# M623.net
KiCad netlist of a schematic drawn in EAGLE
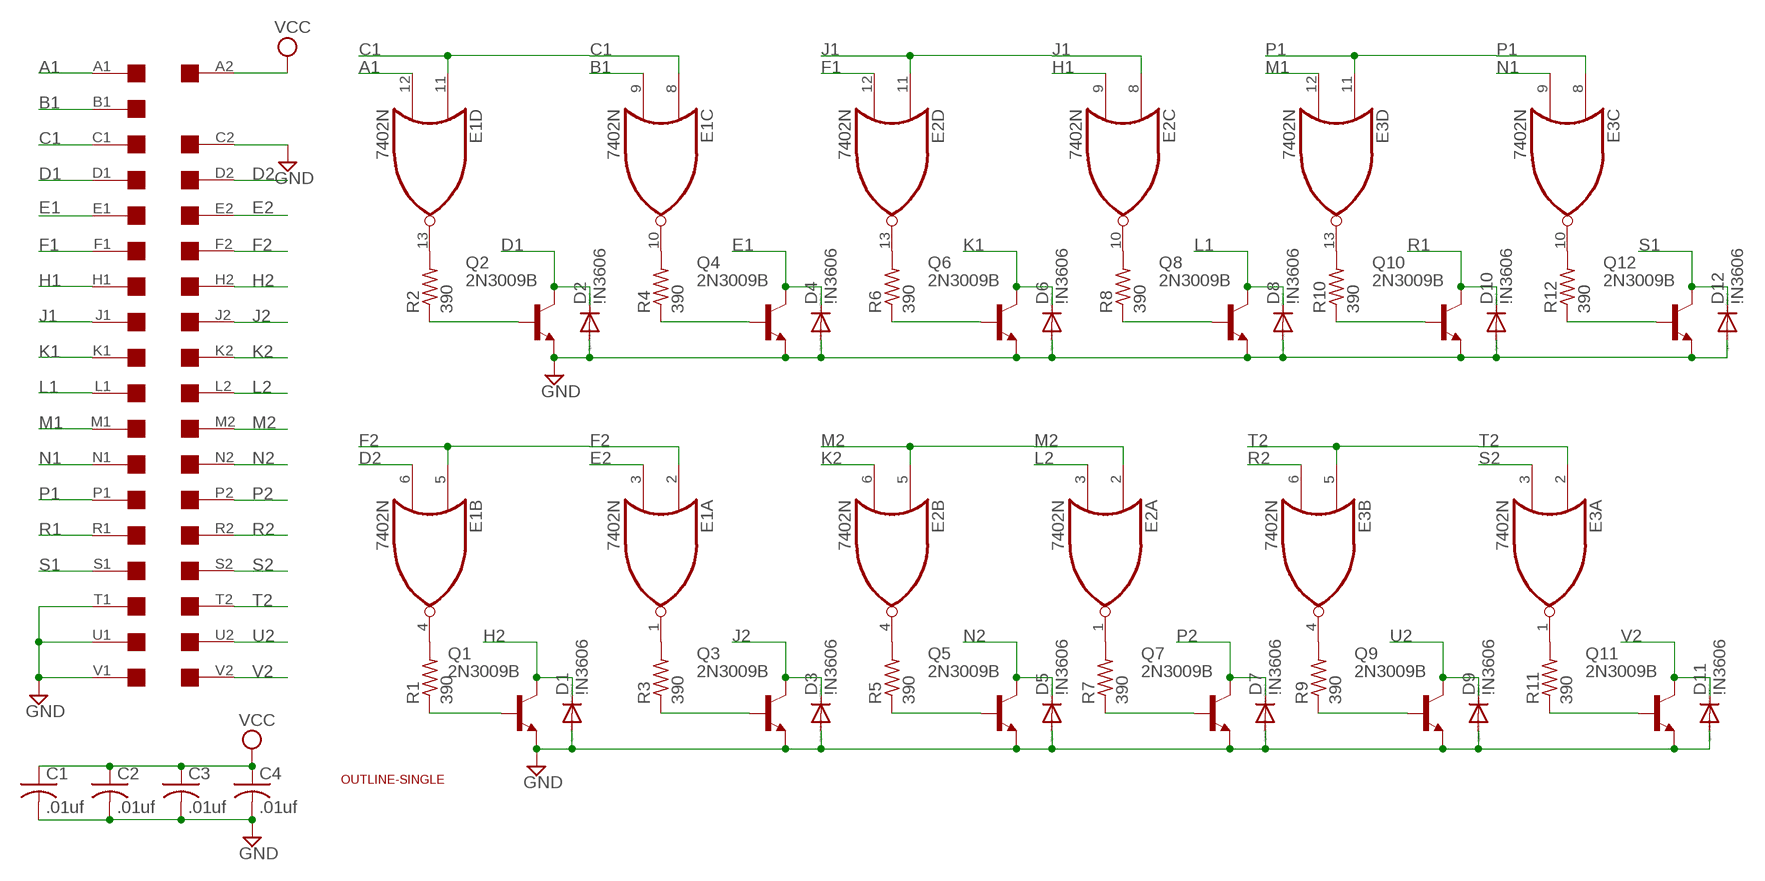
[diagram p0: schematic, sheet 1]

(export (version "E")
  (design (tool "Eeschema 10.0.6"))
  (components
    (comp (ref "C1")
      (value ".01uf")
      (footprint "eagle-import:C050-025X075")
      (libsource (lib "eagle-import") (part "C-US050-025X075"))
    )
    (comp (ref "C2")
      (value ".01uf")
      (footprint "eagle-import:C050-025X075")
      (libsource (lib "eagle-import") (part "C-US050-025X075"))
    )
    (comp (ref "C3")
      (value ".01uf")
      (footprint "eagle-import:C050-025X075")
      (libsource (lib "eagle-import") (part "C-US050-025X075"))
    )
    (comp (ref "C4")
      (value ".01uf")
      (footprint "eagle-import:C050-025X075")
      (libsource (lib "eagle-import") (part "C-US050-025X075"))
    )
    (comp (ref "D1")
      (value "\\!N3606")
      (footprint "eagle-import:DO35-10")
      (libsource (lib "eagle-import") (part "1N4148DO35-10"))
    )
    (comp (ref "D2")
      (value "\\!N3606")
      (footprint "eagle-import:DO35-10")
      (libsource (lib "eagle-import") (part "1N4148DO35-10"))
    )
    (comp (ref "D3")
      (value "\\!N3606")
      (footprint "eagle-import:DO35-10")
      (libsource (lib "eagle-import") (part "1N4148DO35-10"))
    )
    (comp (ref "D4")
      (value "\\!N3606")
      (footprint "eagle-import:DO35-10")
      (libsource (lib "eagle-import") (part "1N4148DO35-10"))
    )
    (comp (ref "D5")
      (value "\\!N3606")
      (footprint "eagle-import:DO35-10")
      (libsource (lib "eagle-import") (part "1N4148DO35-10"))
    )
    (comp (ref "D6")
      (value "\\!N3606")
      (footprint "eagle-import:DO35-10")
      (libsource (lib "eagle-import") (part "1N4148DO35-10"))
    )
    (comp (ref "D7")
      (value "\\!N3606")
      (footprint "eagle-import:DO35-10")
      (libsource (lib "eagle-import") (part "1N4148DO35-10"))
    )
    (comp (ref "D8")
      (value "\\!N3606")
      (footprint "eagle-import:DO35-10")
      (libsource (lib "eagle-import") (part "1N4148DO35-10"))
    )
    (comp (ref "D9")
      (value "\\!N3606")
      (footprint "eagle-import:DO35-10")
      (libsource (lib "eagle-import") (part "1N4148DO35-10"))
    )
    (comp (ref "D10")
      (value "\\!N3606")
      (footprint "eagle-import:DO35-10")
      (libsource (lib "eagle-import") (part "1N4148DO35-10"))
    )
    (comp (ref "D11")
      (value "\\!N3606")
      (footprint "eagle-import:DO35-10")
      (libsource (lib "eagle-import") (part "1N4148DO35-10"))
    )
    (comp (ref "D12")
      (value "\\!N3606")
      (footprint "eagle-import:DO35-10")
      (libsource (lib "eagle-import") (part "1N4148DO35-10"))
    )
    (comp (ref "E1")
      (value "7402N")
      (footprint "eagle-import:DIL14")
      (libsource (lib "eagle-import") (part "7402N"))
    )
    (comp (ref "E2")
      (value "7402N")
      (footprint "eagle-import:DIL14")
      (libsource (lib "eagle-import") (part "7402N"))
    )
    (comp (ref "E3")
      (value "7402N")
      (footprint "eagle-import:DIL14")
      (libsource (lib "eagle-import") (part "7402N"))
    )
    (comp (ref "Q1")
      (value "2N3009B")
      (footprint "eagle-import:TO39")
      (libsource (lib "eagle-import") (part "-NPN-TO39-EBC2N1613"))
    )
    (comp (ref "Q2")
      (value "2N3009B")
      (footprint "eagle-import:TO39")
      (libsource (lib "eagle-import") (part "-NPN-TO39-EBC2N1613"))
    )
    (comp (ref "Q3")
      (value "2N3009B")
      (footprint "eagle-import:TO39")
      (libsource (lib "eagle-import") (part "-NPN-TO39-EBC2N1613"))
    )
    (comp (ref "Q4")
      (value "2N3009B")
      (footprint "eagle-import:TO39")
      (libsource (lib "eagle-import") (part "-NPN-TO39-EBC2N1613"))
    )
    (comp (ref "Q5")
      (value "2N3009B")
      (footprint "eagle-import:TO39")
      (libsource (lib "eagle-import") (part "-NPN-TO39-EBC2N1613"))
    )
    (comp (ref "Q6")
      (value "2N3009B")
      (footprint "eagle-import:TO39")
      (libsource (lib "eagle-import") (part "-NPN-TO39-EBC2N1613"))
    )
    (comp (ref "Q7")
      (value "2N3009B")
      (footprint "eagle-import:TO39")
      (libsource (lib "eagle-import") (part "-NPN-TO39-EBC2N1613"))
    )
    (comp (ref "Q8")
      (value "2N3009B")
      (footprint "eagle-import:TO39")
      (libsource (lib "eagle-import") (part "-NPN-TO39-EBC2N1613"))
    )
    (comp (ref "Q9")
      (value "2N3009B")
      (footprint "eagle-import:TO39")
      (libsource (lib "eagle-import") (part "-NPN-TO39-EBC2N1613"))
    )
    (comp (ref "Q10")
      (value "2N3009B")
      (footprint "eagle-import:TO39")
      (libsource (lib "eagle-import") (part "-NPN-TO39-EBC2N1613"))
    )
    (comp (ref "Q11")
      (value "2N3009B")
      (footprint "eagle-import:TO39")
      (libsource (lib "eagle-import") (part "-NPN-TO39-EBC2N1613"))
    )
    (comp (ref "Q12")
      (value "2N3009B")
      (footprint "eagle-import:TO39")
      (libsource (lib "eagle-import") (part "-NPN-TO39-EBC2N1613"))
    )
    (comp (ref "R1")
      (value "390")
      (footprint "eagle-import:0207_10")
      (libsource (lib "eagle-import") (part "R-US_0207/10"))
    )
    (comp (ref "R2")
      (value "390")
      (footprint "eagle-import:0207_10")
      (libsource (lib "eagle-import") (part "R-US_0207/10"))
    )
    (comp (ref "R3")
      (value "390")
      (footprint "eagle-import:0207_10")
      (libsource (lib "eagle-import") (part "R-US_0207/10"))
    )
    (comp (ref "R4")
      (value "390")
      (footprint "eagle-import:0207_10")
      (libsource (lib "eagle-import") (part "R-US_0207/10"))
    )
    (comp (ref "R5")
      (value "390")
      (footprint "eagle-import:0207_10")
      (libsource (lib "eagle-import") (part "R-US_0207/10"))
    )
    (comp (ref "R6")
      (value "390")
      (footprint "eagle-import:0207_10")
      (libsource (lib "eagle-import") (part "R-US_0207/10"))
    )
    (comp (ref "R7")
      (value "390")
      (footprint "eagle-import:0207_10")
      (libsource (lib "eagle-import") (part "R-US_0207/10"))
    )
    (comp (ref "R8")
      (value "390")
      (footprint "eagle-import:0207_10")
      (libsource (lib "eagle-import") (part "R-US_0207/10"))
    )
    (comp (ref "R9")
      (value "390")
      (footprint "eagle-import:0207_10")
      (libsource (lib "eagle-import") (part "R-US_0207/10"))
    )
    (comp (ref "R10")
      (value "390")
      (footprint "eagle-import:0207_10")
      (libsource (lib "eagle-import") (part "R-US_0207/10"))
    )
    (comp (ref "R11")
      (value "390")
      (footprint "eagle-import:0207_10")
      (libsource (lib "eagle-import") (part "R-US_0207/10"))
    )
    (comp (ref "R12")
      (value "390")
      (footprint "eagle-import:0207_10")
      (libsource (lib "eagle-import") (part "R-US_0207/10"))
    )
    (comp (ref "U$1")
      (value "OUTLINE-SINGLE")
      (footprint "eagle-import:SINGLE")
      (libsource (lib "eagle-import") (part "OUTLINE-SINGLE"))
    )
    (comp (ref "U$4")
      (value "SINGLE")
      (footprint "eagle-import:EDGE-CON2")
      (libsource (lib "eagle-import") (part "SINGLE"))
    )
  )
  (nets
    (net (code "1") (name "/A1") (class "Default")
      (node (ref "E1") (pin "12") (pinfunction "I1_12") (pintype "input"))
      (node (ref "U$4") (pin "A1") (pinfunction "1_A1") (pintype "bidirectional"))
    )
    (net (code "2") (name "/B1") (class "Default")
      (node (ref "E1") (pin "9") (pinfunction "I1_9") (pintype "input"))
      (node (ref "U$4") (pin "B1") (pinfunction "1_B1") (pintype "bidirectional"))
    )
    (net (code "3") (name "/C1") (class "Default")
      (node (ref "E1") (pin "11") (pinfunction "I0_11") (pintype "input"))
      (node (ref "E1") (pin "8") (pinfunction "I0_8") (pintype "input"))
      (node (ref "U$4") (pin "C1") (pinfunction "1_C1") (pintype "bidirectional"))
    )
    (net (code "4") (name "/D1") (class "Default")
      (node (ref "D2") (pin "C") (pinfunction "C_C") (pintype "passive"))
      (node (ref "Q2") (pin "3") (pinfunction "C_3") (pintype "passive"))
      (node (ref "U$4") (pin "D1") (pinfunction "1_D1") (pintype "bidirectional"))
    )
    (net (code "5") (name "/D2") (class "Default")
      (node (ref "E1") (pin "6") (pinfunction "I1_6") (pintype "input"))
      (node (ref "U$4") (pin "D2") (pinfunction "1_D2") (pintype "bidirectional"))
    )
    (net (code "6") (name "/E1") (class "Default")
      (node (ref "D4") (pin "C") (pinfunction "C_C") (pintype "passive"))
      (node (ref "Q4") (pin "3") (pinfunction "C_3") (pintype "passive"))
      (node (ref "U$4") (pin "E1") (pinfunction "1_E1") (pintype "bidirectional"))
    )
    (net (code "7") (name "/E2") (class "Default")
      (node (ref "E1") (pin "3") (pinfunction "I1_3") (pintype "input"))
      (node (ref "U$4") (pin "E2") (pinfunction "1_E2") (pintype "bidirectional"))
    )
    (net (code "8") (name "/F1") (class "Default")
      (node (ref "E2") (pin "12") (pinfunction "I1_12") (pintype "input"))
      (node (ref "U$4") (pin "F1") (pinfunction "1_F1") (pintype "bidirectional"))
    )
    (net (code "9") (name "/F2") (class "Default")
      (node (ref "E1") (pin "2") (pinfunction "I0_2") (pintype "input"))
      (node (ref "E1") (pin "5") (pinfunction "I0_5") (pintype "input"))
      (node (ref "U$4") (pin "F2") (pinfunction "1_F2") (pintype "bidirectional"))
    )
    (net (code "10") (name "/H1") (class "Default")
      (node (ref "E2") (pin "9") (pinfunction "I1_9") (pintype "input"))
      (node (ref "U$4") (pin "H1") (pinfunction "1_H1") (pintype "bidirectional"))
    )
    (net (code "11") (name "/H2") (class "Default")
      (node (ref "D1") (pin "C") (pinfunction "C_C") (pintype "passive"))
      (node (ref "Q1") (pin "3") (pinfunction "C_3") (pintype "passive"))
      (node (ref "U$4") (pin "H2") (pinfunction "1_H2") (pintype "bidirectional"))
    )
    (net (code "12") (name "/J1") (class "Default")
      (node (ref "E2") (pin "11") (pinfunction "I0_11") (pintype "input"))
      (node (ref "E2") (pin "8") (pinfunction "I0_8") (pintype "input"))
      (node (ref "U$4") (pin "J1") (pinfunction "1_J1") (pintype "bidirectional"))
    )
    (net (code "13") (name "/J2") (class "Default")
      (node (ref "D3") (pin "C") (pinfunction "C_C") (pintype "passive"))
      (node (ref "Q3") (pin "3") (pinfunction "C_3") (pintype "passive"))
      (node (ref "U$4") (pin "J2") (pinfunction "1_J2") (pintype "bidirectional"))
    )
    (net (code "14") (name "/K1") (class "Default")
      (node (ref "D6") (pin "C") (pinfunction "C_C") (pintype "passive"))
      (node (ref "Q6") (pin "3") (pinfunction "C_3") (pintype "passive"))
      (node (ref "U$4") (pin "K1") (pinfunction "1_K1") (pintype "bidirectional"))
    )
    (net (code "15") (name "/K2") (class "Default")
      (node (ref "E2") (pin "6") (pinfunction "I1_6") (pintype "input"))
      (node (ref "U$4") (pin "K2") (pinfunction "1_K2") (pintype "bidirectional"))
    )
    (net (code "16") (name "/L1") (class "Default")
      (node (ref "D8") (pin "C") (pinfunction "C_C") (pintype "passive"))
      (node (ref "Q8") (pin "3") (pinfunction "C_3") (pintype "passive"))
      (node (ref "U$4") (pin "L1") (pinfunction "1_L1") (pintype "bidirectional"))
    )
    (net (code "17") (name "/L2") (class "Default")
      (node (ref "E2") (pin "3") (pinfunction "I1_3") (pintype "input"))
      (node (ref "U$4") (pin "L2") (pinfunction "1_L2") (pintype "bidirectional"))
    )
    (net (code "18") (name "/M1") (class "Default")
      (node (ref "E3") (pin "12") (pinfunction "I1_12") (pintype "input"))
      (node (ref "U$4") (pin "M1") (pinfunction "1_M1") (pintype "bidirectional"))
    )
    (net (code "19") (name "/M2") (class "Default")
      (node (ref "E2") (pin "2") (pinfunction "I0_2") (pintype "input"))
      (node (ref "E2") (pin "5") (pinfunction "I0_5") (pintype "input"))
      (node (ref "U$4") (pin "M2") (pinfunction "1_M2") (pintype "bidirectional"))
    )
    (net (code "20") (name "/N1") (class "Default")
      (node (ref "E3") (pin "9") (pinfunction "I1_9") (pintype "input"))
      (node (ref "U$4") (pin "N1") (pinfunction "1_N1") (pintype "bidirectional"))
    )
    (net (code "21") (name "/N2") (class "Default")
      (node (ref "D5") (pin "C") (pinfunction "C_C") (pintype "passive"))
      (node (ref "Q5") (pin "3") (pinfunction "C_3") (pintype "passive"))
      (node (ref "U$4") (pin "N2") (pinfunction "1_N2") (pintype "bidirectional"))
    )
    (net (code "22") (name "/P1") (class "Default")
      (node (ref "E3") (pin "11") (pinfunction "I0_11") (pintype "input"))
      (node (ref "E3") (pin "8") (pinfunction "I0_8") (pintype "input"))
      (node (ref "U$4") (pin "P1") (pinfunction "1_P1") (pintype "bidirectional"))
    )
    (net (code "23") (name "/P2") (class "Default")
      (node (ref "D7") (pin "C") (pinfunction "C_C") (pintype "passive"))
      (node (ref "Q7") (pin "3") (pinfunction "C_3") (pintype "passive"))
      (node (ref "U$4") (pin "P2") (pinfunction "1_P2") (pintype "bidirectional"))
    )
    (net (code "24") (name "/R1") (class "Default")
      (node (ref "D10") (pin "C") (pinfunction "C_C") (pintype "passive"))
      (node (ref "Q10") (pin "3") (pinfunction "C_3") (pintype "passive"))
      (node (ref "U$4") (pin "R1") (pinfunction "1_R1") (pintype "bidirectional"))
    )
    (net (code "25") (name "/R2") (class "Default")
      (node (ref "E3") (pin "6") (pinfunction "I1_6") (pintype "input"))
      (node (ref "U$4") (pin "R2") (pinfunction "1_R2") (pintype "bidirectional"))
    )
    (net (code "26") (name "/S1") (class "Default")
      (node (ref "D12") (pin "C") (pinfunction "C_C") (pintype "passive"))
      (node (ref "Q12") (pin "3") (pinfunction "C_3") (pintype "passive"))
      (node (ref "U$4") (pin "S1") (pinfunction "1_S1") (pintype "bidirectional"))
    )
    (net (code "27") (name "/S2") (class "Default")
      (node (ref "E3") (pin "3") (pinfunction "I1_3") (pintype "input"))
      (node (ref "U$4") (pin "S2") (pinfunction "1_S2") (pintype "bidirectional"))
    )
    (net (code "28") (name "/T2") (class "Default")
      (node (ref "E3") (pin "2") (pinfunction "I0_2") (pintype "input"))
      (node (ref "E3") (pin "5") (pinfunction "I0_5") (pintype "input"))
      (node (ref "U$4") (pin "T2") (pinfunction "1_T2") (pintype "bidirectional"))
    )
    (net (code "29") (name "/U2") (class "Default")
      (node (ref "D9") (pin "C") (pinfunction "C_C") (pintype "passive"))
      (node (ref "Q9") (pin "3") (pinfunction "C_3") (pintype "passive"))
      (node (ref "U$4") (pin "U2") (pinfunction "1_U2") (pintype "bidirectional"))
    )
    (net (code "30") (name "/V2") (class "Default")
      (node (ref "D11") (pin "C") (pinfunction "C_C") (pintype "passive"))
      (node (ref "Q11") (pin "3") (pinfunction "C_3") (pintype "passive"))
      (node (ref "U$4") (pin "V2") (pinfunction "1_V2") (pintype "bidirectional"))
    )
    (net (code "31") (name "GND") (class "Default")
      (node (ref "C1") (pin "2") (pinfunction "2_2") (pintype "passive"))
      (node (ref "C2") (pin "2") (pinfunction "2_2") (pintype "passive"))
      (node (ref "C3") (pin "2") (pinfunction "2_2") (pintype "passive"))
      (node (ref "C4") (pin "2") (pinfunction "2_2") (pintype "passive"))
      (node (ref "D1") (pin "A") (pinfunction "A_A") (pintype "passive"))
      (node (ref "D10") (pin "A") (pinfunction "A_A") (pintype "passive"))
      (node (ref "D11") (pin "A") (pinfunction "A_A") (pintype "passive"))
      (node (ref "D12") (pin "A") (pinfunction "A_A") (pintype "passive"))
      (node (ref "D2") (pin "A") (pinfunction "A_A") (pintype "passive"))
      (node (ref "D3") (pin "A") (pinfunction "A_A") (pintype "passive"))
      (node (ref "D4") (pin "A") (pinfunction "A_A") (pintype "passive"))
      (node (ref "D5") (pin "A") (pinfunction "A_A") (pintype "passive"))
      (node (ref "D6") (pin "A") (pinfunction "A_A") (pintype "passive"))
      (node (ref "D7") (pin "A") (pinfunction "A_A") (pintype "passive"))
      (node (ref "D8") (pin "A") (pinfunction "A_A") (pintype "passive"))
      (node (ref "D9") (pin "A") (pinfunction "A_A") (pintype "passive"))
      (node (ref "Q1") (pin "1") (pinfunction "E_1") (pintype "passive"))
      (node (ref "Q10") (pin "1") (pinfunction "E_1") (pintype "passive"))
      (node (ref "Q11") (pin "1") (pinfunction "E_1") (pintype "passive"))
      (node (ref "Q12") (pin "1") (pinfunction "E_1") (pintype "passive"))
      (node (ref "Q2") (pin "1") (pinfunction "E_1") (pintype "passive"))
      (node (ref "Q3") (pin "1") (pinfunction "E_1") (pintype "passive"))
      (node (ref "Q4") (pin "1") (pinfunction "E_1") (pintype "passive"))
      (node (ref "Q5") (pin "1") (pinfunction "E_1") (pintype "passive"))
      (node (ref "Q6") (pin "1") (pinfunction "E_1") (pintype "passive"))
      (node (ref "Q7") (pin "1") (pinfunction "E_1") (pintype "passive"))
      (node (ref "Q8") (pin "1") (pinfunction "E_1") (pintype "passive"))
      (node (ref "Q9") (pin "1") (pinfunction "E_1") (pintype "passive"))
      (node (ref "U$4") (pin "C2") (pinfunction "1_C2") (pintype "bidirectional"))
      (node (ref "U$4") (pin "T1") (pinfunction "1_T1") (pintype "bidirectional"))
      (node (ref "U$4") (pin "U1") (pinfunction "1_U1") (pintype "bidirectional"))
      (node (ref "U$4") (pin "V1") (pinfunction "1_V1") (pintype "bidirectional"))
    )
    (net (code "32") (name "Net-(E1A-O)") (class "Default")
      (node (ref "E1") (pin "1") (pinfunction "O_1") (pintype "output"))
      (node (ref "R3") (pin "2") (pinfunction "2_2") (pintype "passive"))
    )
    (net (code "33") (name "Net-(E1B-O)") (class "Default")
      (node (ref "E1") (pin "4") (pinfunction "O_4") (pintype "output"))
      (node (ref "R1") (pin "2") (pinfunction "2_2") (pintype "passive"))
    )
    (net (code "34") (name "Net-(E1C-O)") (class "Default")
      (node (ref "E1") (pin "10") (pinfunction "O_10") (pintype "output"))
      (node (ref "R4") (pin "2") (pinfunction "2_2") (pintype "passive"))
    )
    (net (code "35") (name "Net-(E1D-O)") (class "Default")
      (node (ref "E1") (pin "13") (pinfunction "O_13") (pintype "output"))
      (node (ref "R2") (pin "2") (pinfunction "2_2") (pintype "passive"))
    )
    (net (code "36") (name "Net-(E2A-O)") (class "Default")
      (node (ref "E2") (pin "1") (pinfunction "O_1") (pintype "output"))
      (node (ref "R7") (pin "2") (pinfunction "2_2") (pintype "passive"))
    )
    (net (code "37") (name "Net-(E2B-O)") (class "Default")
      (node (ref "E2") (pin "4") (pinfunction "O_4") (pintype "output"))
      (node (ref "R5") (pin "2") (pinfunction "2_2") (pintype "passive"))
    )
    (net (code "38") (name "Net-(E2C-O)") (class "Default")
      (node (ref "E2") (pin "10") (pinfunction "O_10") (pintype "output"))
      (node (ref "R8") (pin "2") (pinfunction "2_2") (pintype "passive"))
    )
    (net (code "39") (name "Net-(E2D-O)") (class "Default")
      (node (ref "E2") (pin "13") (pinfunction "O_13") (pintype "output"))
      (node (ref "R6") (pin "2") (pinfunction "2_2") (pintype "passive"))
    )
    (net (code "40") (name "Net-(E3A-O)") (class "Default")
      (node (ref "E3") (pin "1") (pinfunction "O_1") (pintype "output"))
      (node (ref "R11") (pin "2") (pinfunction "2_2") (pintype "passive"))
    )
    (net (code "41") (name "Net-(E3B-O)") (class "Default")
      (node (ref "E3") (pin "4") (pinfunction "O_4") (pintype "output"))
      (node (ref "R9") (pin "2") (pinfunction "2_2") (pintype "passive"))
    )
    (net (code "42") (name "Net-(E3C-O)") (class "Default")
      (node (ref "E3") (pin "10") (pinfunction "O_10") (pintype "output"))
      (node (ref "R12") (pin "2") (pinfunction "2_2") (pintype "passive"))
    )
    (net (code "43") (name "Net-(E3D-O)") (class "Default")
      (node (ref "E3") (pin "13") (pinfunction "O_13") (pintype "output"))
      (node (ref "R10") (pin "2") (pinfunction "2_2") (pintype "passive"))
    )
    (net (code "44") (name "Net-(Q1-B)") (class "Default")
      (node (ref "Q1") (pin "2") (pinfunction "B_2") (pintype "passive"))
      (node (ref "R1") (pin "1") (pinfunction "1_1") (pintype "passive"))
    )
    (net (code "45") (name "Net-(Q2-B)") (class "Default")
      (node (ref "Q2") (pin "2") (pinfunction "B_2") (pintype "passive"))
      (node (ref "R2") (pin "1") (pinfunction "1_1") (pintype "passive"))
    )
    (net (code "46") (name "Net-(Q3-B)") (class "Default")
      (node (ref "Q3") (pin "2") (pinfunction "B_2") (pintype "passive"))
      (node (ref "R3") (pin "1") (pinfunction "1_1") (pintype "passive"))
    )
    (net (code "47") (name "Net-(Q4-B)") (class "Default")
      (node (ref "Q4") (pin "2") (pinfunction "B_2") (pintype "passive"))
      (node (ref "R4") (pin "1") (pinfunction "1_1") (pintype "passive"))
    )
    (net (code "48") (name "Net-(Q5-B)") (class "Default")
      (node (ref "Q5") (pin "2") (pinfunction "B_2") (pintype "passive"))
      (node (ref "R5") (pin "1") (pinfunction "1_1") (pintype "passive"))
    )
    (net (code "49") (name "Net-(Q6-B)") (class "Default")
      (node (ref "Q6") (pin "2") (pinfunction "B_2") (pintype "passive"))
      (node (ref "R6") (pin "1") (pinfunction "1_1") (pintype "passive"))
    )
    (net (code "50") (name "Net-(Q7-B)") (class "Default")
      (node (ref "Q7") (pin "2") (pinfunction "B_2") (pintype "passive"))
      (node (ref "R7") (pin "1") (pinfunction "1_1") (pintype "passive"))
    )
    (net (code "51") (name "Net-(Q8-B)") (class "Default")
      (node (ref "Q8") (pin "2") (pinfunction "B_2") (pintype "passive"))
      (node (ref "R8") (pin "1") (pinfunction "1_1") (pintype "passive"))
    )
    (net (code "52") (name "Net-(Q9-B)") (class "Default")
      (node (ref "Q9") (pin "2") (pinfunction "B_2") (pintype "passive"))
      (node (ref "R9") (pin "1") (pinfunction "1_1") (pintype "passive"))
    )
    (net (code "53") (name "Net-(Q10-B)") (class "Default")
      (node (ref "Q10") (pin "2") (pinfunction "B_2") (pintype "passive"))
      (node (ref "R10") (pin "1") (pinfunction "1_1") (pintype "passive"))
    )
    (net (code "54") (name "Net-(Q11-B)") (class "Default")
      (node (ref "Q11") (pin "2") (pinfunction "B_2") (pintype "passive"))
      (node (ref "R11") (pin "1") (pinfunction "1_1") (pintype "passive"))
    )
    (net (code "55") (name "Net-(Q12-B)") (class "Default")
      (node (ref "Q12") (pin "2") (pinfunction "B_2") (pintype "passive"))
      (node (ref "R12") (pin "1") (pinfunction "1_1") (pintype "passive"))
    )
    (net (code "56") (name "VCC") (class "Default")
      (node (ref "C1") (pin "1") (pinfunction "1_1") (pintype "passive"))
      (node (ref "C2") (pin "1") (pinfunction "1_1") (pintype "passive"))
      (node (ref "C3") (pin "1") (pinfunction "1_1") (pintype "passive"))
      (node (ref "C4") (pin "1") (pinfunction "1_1") (pintype "passive"))
      (node (ref "U$4") (pin "A2") (pinfunction "1_A2") (pintype "bidirectional"))
    )
  )
)
